# FT232RL_Circuit.net
KiCad netlist of a schematic drawn in EAGLE
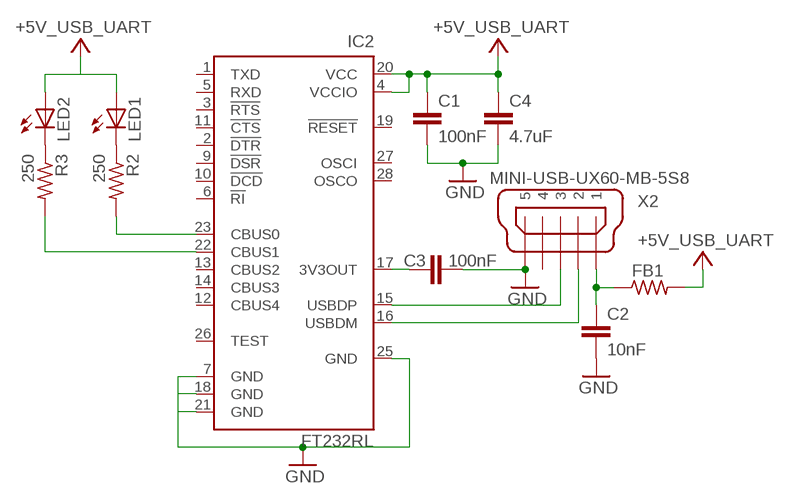
[diagram p0: schematic, sheet 1]

(export (version "E")
  (design (tool "Eeschema 10.0.6"))
  (components
    (comp (ref "C1")
      (value "100nF")
      (footprint "eagle-import:C0603")
      (libsource (lib "eagle-import") (part "C-EUC0603"))
    )
    (comp (ref "C2")
      (value "10nF")
      (footprint "eagle-import:C0603")
      (libsource (lib "eagle-import") (part "C-EUC0603"))
    )
    (comp (ref "C3")
      (value "100nF")
      (footprint "eagle-import:C0603")
      (libsource (lib "eagle-import") (part "C-EUC0603"))
    )
    (comp (ref "C4")
      (value "4.7uF")
      (footprint "eagle-import:C0603")
      (libsource (lib "eagle-import") (part "C-EUC0603"))
    )
    (comp (ref "FB1")
      (value "R-US_R0603")
      (footprint "eagle-import:R0603")
      (libsource (lib "eagle-import") (part "R-US_R0603"))
    )
    (comp (ref "IC2")
      (value "FT232RL")
      (footprint "eagle-import:SSOP28")
      (libsource (lib "eagle-import") (part "FT232RL"))
    )
    (comp (ref "LED1")
      (value "LEDCHIPLED_0603")
      (footprint "eagle-import:CHIPLED_0603")
      (libsource (lib "eagle-import") (part "LEDCHIPLED_0603"))
    )
    (comp (ref "LED2")
      (value "LEDCHIPLED_0603")
      (footprint "eagle-import:CHIPLED_0603")
      (libsource (lib "eagle-import") (part "LEDCHIPLED_0603"))
    )
    (comp (ref "R2")
      (value "250")
      (footprint "eagle-import:R0603")
      (libsource (lib "eagle-import") (part "R-US_R0603"))
    )
    (comp (ref "R3")
      (value "250")
      (footprint "eagle-import:R0603")
      (libsource (lib "eagle-import") (part "R-US_R0603"))
    )
    (comp (ref "X2")
      (value "MINI-USB-UX60-MB-5S8")
      (footprint "eagle-import:UX60-MB-5S8")
      (libsource (lib "eagle-import") (part "MINI-USB-UX60-MB-5S8"))
    )
  )
  (nets
    (net (code "1") (name "+5V_USB_UART") (class "Default")
      (node (ref "C1") (pin "1") (pinfunction "1_1") (pintype "passive"))
      (node (ref "C4") (pin "1") (pinfunction "1_1") (pintype "passive"))
      (node (ref "FB1") (pin "2") (pinfunction "2_2") (pintype "passive"))
      (node (ref "IC2") (pin "20") (pinfunction "VCC_20") (pintype "power_in"))
      (node (ref "IC2") (pin "4") (pinfunction "VCCIO_4") (pintype "power_in"))
      (node (ref "LED1") (pin "A") (pinfunction "A_A") (pintype "passive"))
      (node (ref "LED2") (pin "A") (pinfunction "A_A") (pintype "passive"))
    )
    (net (code "2") (name "GND") (class "Default")
      (node (ref "C1") (pin "2") (pinfunction "2_2") (pintype "passive"))
      (node (ref "C2") (pin "2") (pinfunction "2_2") (pintype "passive"))
      (node (ref "C3") (pin "2") (pinfunction "2_2") (pintype "passive"))
      (node (ref "C4") (pin "2") (pinfunction "2_2") (pintype "passive"))
      (node (ref "IC2") (pin "18") (pinfunction "GND_18") (pintype "power_in"))
      (node (ref "IC2") (pin "21") (pinfunction "GND_21") (pintype "power_in"))
      (node (ref "IC2") (pin "25") (pinfunction "GND_25") (pintype "power_in"))
      (node (ref "IC2") (pin "7") (pinfunction "GND_7") (pintype "power_in"))
      (node (ref "X2") (pin "5") (pinfunction "5_5") (pintype "input"))
    )
    (net (code "3") (name "Net-(C2-Pad1)") (class "Default")
      (node (ref "C2") (pin "1") (pinfunction "1_1") (pintype "passive"))
      (node (ref "FB1") (pin "1") (pinfunction "1_1") (pintype "passive"))
      (node (ref "X2") (pin "1") (pinfunction "1_1") (pintype "input"))
    )
    (net (code "4") (name "Net-(IC2-3V3OUT)") (class "Default")
      (node (ref "C3") (pin "1") (pinfunction "1_1") (pintype "passive"))
      (node (ref "IC2") (pin "17") (pinfunction "3V3OUT_17") (pintype "output"))
    )
    (net (code "5") (name "Net-(IC2-CBUS0)") (class "Default")
      (node (ref "IC2") (pin "23") (pinfunction "CBUS0_23") (pintype "bidirectional"))
      (node (ref "R2") (pin "2") (pinfunction "2_2") (pintype "passive"))
    )
    (net (code "6") (name "Net-(IC2-CBUS1)") (class "Default")
      (node (ref "IC2") (pin "22") (pinfunction "CBUS1_22") (pintype "bidirectional"))
      (node (ref "R3") (pin "2") (pinfunction "2_2") (pintype "passive"))
    )
    (net (code "7") (name "Net-(IC2-USBDM)") (class "Default")
      (node (ref "IC2") (pin "16") (pinfunction "USBDM_16") (pintype "bidirectional"))
      (node (ref "X2") (pin "2") (pinfunction "2_2") (pintype "input"))
    )
    (net (code "8") (name "Net-(IC2-USBDP)") (class "Default")
      (node (ref "IC2") (pin "15") (pinfunction "USBDP_15") (pintype "bidirectional"))
      (node (ref "X2") (pin "3") (pinfunction "3_3") (pintype "input"))
    )
    (net (code "9") (name "Net-(LED1-PadC)") (class "Default")
      (node (ref "LED1") (pin "C") (pinfunction "C_C") (pintype "passive"))
      (node (ref "R2") (pin "1") (pinfunction "1_1") (pintype "passive"))
    )
    (net (code "10") (name "Net-(LED2-PadC)") (class "Default")
      (node (ref "LED2") (pin "C") (pinfunction "C_C") (pintype "passive"))
      (node (ref "R3") (pin "1") (pinfunction "1_1") (pintype "passive"))
    )
    (net (code "11") (name "unconnected-(IC2-CBUS2-Pad13)") (class "Default")
      (node (ref "IC2") (pin "13") (pinfunction "CBUS2_13") (pintype "bidirectional"))
    )
    (net (code "12") (name "unconnected-(IC2-CBUS3-Pad14)") (class "Default")
      (node (ref "IC2") (pin "14") (pinfunction "CBUS3_14") (pintype "bidirectional"))
    )
    (net (code "13") (name "unconnected-(IC2-CBUS4-Pad12)") (class "Default")
      (node (ref "IC2") (pin "12") (pinfunction "CBUS4_12") (pintype "bidirectional"))
    )
    (net (code "14") (name "unconnected-(IC2-OSCI-Pad27)") (class "Default")
      (node (ref "IC2") (pin "27") (pinfunction "OSCI_27") (pintype "input"))
    )
    (net (code "15") (name "unconnected-(IC2-OSCO-Pad28)") (class "Default")
      (node (ref "IC2") (pin "28") (pinfunction "OSCO_28") (pintype "output"))
    )
    (net (code "16") (name "unconnected-(IC2-RXD-Pad5)") (class "Default")
      (node (ref "IC2") (pin "5") (pinfunction "RXD_5") (pintype "input"))
    )
    (net (code "17") (name "unconnected-(IC2-TEST-Pad26)") (class "Default")
      (node (ref "IC2") (pin "26") (pinfunction "TEST_26") (pintype "input"))
    )
    (net (code "18") (name "unconnected-(IC2-TXD-Pad1)") (class "Default")
      (node (ref "IC2") (pin "1") (pinfunction "TXD_1") (pintype "output"))
    )
    (net (code "19") (name "unconnected-(IC2-~{CTS}-Pad11)") (class "Default")
      (node (ref "IC2") (pin "11") (pinfunction "~{CTS}_11") (pintype "input"))
    )
    (net (code "20") (name "unconnected-(IC2-~{DCD}-Pad10)") (class "Default")
      (node (ref "IC2") (pin "10") (pinfunction "~{DCD}_10") (pintype "input"))
    )
    (net (code "21") (name "unconnected-(IC2-~{DSR}-Pad9)") (class "Default")
      (node (ref "IC2") (pin "9") (pinfunction "~{DSR}_9") (pintype "input"))
    )
    (net (code "22") (name "unconnected-(IC2-~{DTR}-Pad2)") (class "Default")
      (node (ref "IC2") (pin "2") (pinfunction "~{DTR}_2") (pintype "output"))
    )
    (net (code "23") (name "unconnected-(IC2-~{RESET}-Pad19)") (class "Default")
      (node (ref "IC2") (pin "19") (pinfunction "~{RESET}_19") (pintype "input"))
    )
    (net (code "24") (name "unconnected-(IC2-~{RI}-Pad6)") (class "Default")
      (node (ref "IC2") (pin "6") (pinfunction "~{RI}_6") (pintype "input"))
    )
    (net (code "25") (name "unconnected-(IC2-~{RTS}-Pad3)") (class "Default")
      (node (ref "IC2") (pin "3") (pinfunction "~{RTS}_3") (pintype "output"))
    )
    (net (code "26") (name "unconnected-(X2-Pad4)") (class "Default")
      (node (ref "X2") (pin "4") (pinfunction "4_4") (pintype "input"))
    )
  )
)
